# Domino_I2S.net
KiCad netlist of a schematic drawn in EAGLE
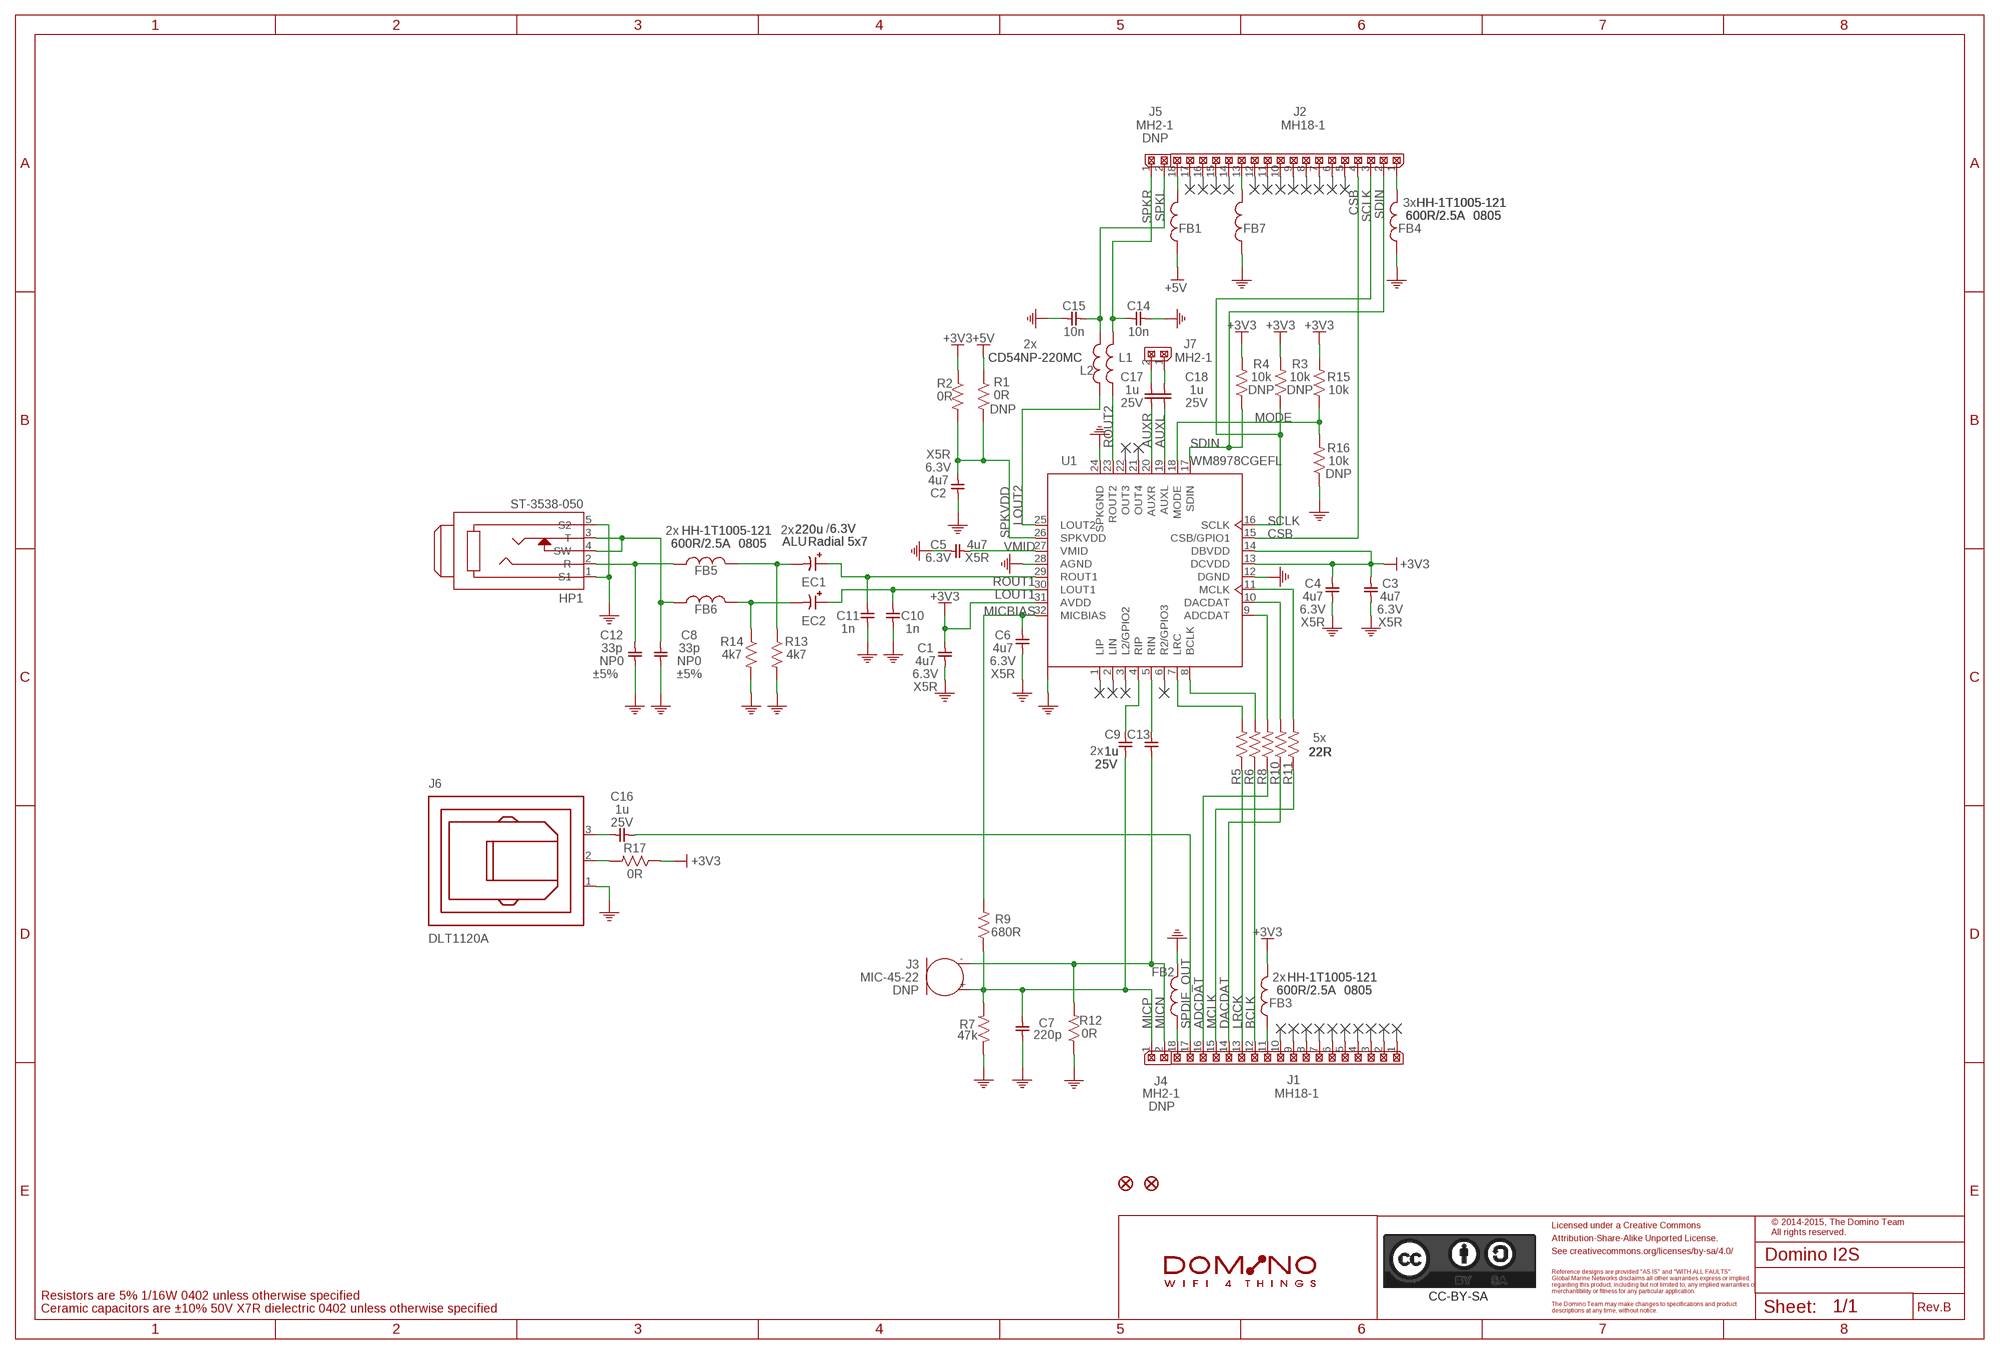
[diagram p0: schematic, sheet 1]

(export (version "E")
  (design (tool "Eeschema 10.0.6"))
  (components
    (comp (ref "C1")
      (value "4u7")
      (footprint "eagle-import:C0402")
      (fields
        (field (name "PARTNO") "C0402_4u7_X5R_10%_CER_6V3")
        (field (name "TC") "X5R")
        (field (name "VOLT") "6.3V")
      )
      (libsource (lib "eagle-import") (part "CAP_0402"))
    )
    (comp (ref "C2")
      (value "4u7")
      (footprint "eagle-import:C0402")
      (fields
        (field (name "PARTNO") "C0402_4u7_X5R_10%_CER_6V3")
        (field (name "TC") "X5R")
        (field (name "VOLT") "6.3V")
      )
      (libsource (lib "eagle-import") (part "CAP_0402"))
    )
    (comp (ref "C3")
      (value "4u7")
      (footprint "eagle-import:C0402")
      (fields
        (field (name "PARTNO") "C0402_4u7_X5R_10%_CER_6V3")
        (field (name "TC") "X5R")
        (field (name "VOLT") "6.3V")
      )
      (libsource (lib "eagle-import") (part "CAP_0402"))
    )
    (comp (ref "C4")
      (value "4u7")
      (footprint "eagle-import:C0402")
      (fields
        (field (name "PARTNO") "C0402_4u7_X5R_10%_CER_6V3")
        (field (name "TC") "X5R")
        (field (name "VOLT") "6.3V")
      )
      (libsource (lib "eagle-import") (part "CAP_0402"))
    )
    (comp (ref "C5")
      (value "4u7")
      (footprint "eagle-import:C0402")
      (fields
        (field (name "PARTNO") "C0402_4u7_X5R_10%_CER_6V3")
        (field (name "TC") "X5R")
        (field (name "VOLT") "6.3V")
      )
      (libsource (lib "eagle-import") (part "CAP_0402"))
    )
    (comp (ref "C6")
      (value "4u7")
      (footprint "eagle-import:C0402")
      (fields
        (field (name "PARTNO") "C0402_4u7_X5R_10%_CER_6V3")
        (field (name "TC") "X5R")
        (field (name "VOLT") "6.3V")
      )
      (libsource (lib "eagle-import") (part "CAP_0402"))
    )
    (comp (ref "C7")
      (value "220p")
      (footprint "eagle-import:C0402")
      (fields (field (name "PARTNO") "C0402_220p_X7R_10%_CER_50V"))
      (libsource (lib "eagle-import") (part "CAP_0402"))
    )
    (comp (ref "C8")
      (value "33p")
      (footprint "eagle-import:C0402")
      (fields
        (field (name "PARTNO") "C0402_33p_NP0_5%_CER_50V")
        (field (name "TC") "NP0")
        (field (name "TOL") "±5%")
      )
      (libsource (lib "eagle-import") (part "CAP_0402"))
    )
    (comp (ref "C9")
      (value "1u")
      (footprint "eagle-import:C0402")
      (fields (field (name "PARTNO") "C0402_1u_X7R_10%_CER_25V") (field (name "VOLT") "25V"))
      (libsource (lib "eagle-import") (part "CAP_0402"))
    )
    (comp (ref "C10")
      (value "1n")
      (footprint "eagle-import:C0402")
      (fields (field (name "PARTNO") "C0402_1n_X7R_10%_CER_50V"))
      (libsource (lib "eagle-import") (part "CAP_0402"))
    )
    (comp (ref "C11")
      (value "1n")
      (footprint "eagle-import:C0402")
      (fields (field (name "PARTNO") "C0402_1n_X7R_10%_CER_50V"))
      (libsource (lib "eagle-import") (part "CAP_0402"))
    )
    (comp (ref "C12")
      (value "33p")
      (footprint "eagle-import:C0402")
      (fields
        (field (name "PARTNO") "C0402_33p_NP0_5%_CER_50V")
        (field (name "TC") "NP0")
        (field (name "TOL") "±5%")
      )
      (libsource (lib "eagle-import") (part "CAP_0402"))
    )
    (comp (ref "C13")
      (value "1u")
      (footprint "eagle-import:C0402")
      (fields (field (name "PARTNO") "C0402_1u_X7R_10%_CER_25V") (field (name "VOLT") "25V"))
      (libsource (lib "eagle-import") (part "CAP_0402"))
    )
    (comp (ref "C14")
      (value "10n")
      (footprint "eagle-import:C0402")
      (fields (field (name "PARTNO") "C0402_10n_X7R_10%_CER_50V"))
      (libsource (lib "eagle-import") (part "CAP_0402"))
    )
    (comp (ref "C15")
      (value "10n")
      (footprint "eagle-import:C0402")
      (fields (field (name "PARTNO") "C0402_10n_X7R_10%_CER_50V"))
      (libsource (lib "eagle-import") (part "CAP_0402"))
    )
    (comp (ref "C16")
      (value "1u")
      (footprint "eagle-import:C0402")
      (fields (field (name "PARTNO") "C0402_1u_X7R_10%_CER_25V") (field (name "VOLT") "25V"))
      (libsource (lib "eagle-import") (part "CAP_0402"))
    )
    (comp (ref "C17")
      (value "1u")
      (footprint "eagle-import:C0402")
      (fields (field (name "PARTNO") "C0402_1u_X7R_10%_CER_25V") (field (name "VOLT") "25V"))
      (libsource (lib "eagle-import") (part "CAP_0402"))
    )
    (comp (ref "C18")
      (value "1u")
      (footprint "eagle-import:C0402")
      (fields (field (name "PARTNO") "C0402_1u_X7R_10%_CER_25V") (field (name "VOLT") "25V"))
      (libsource (lib "eagle-import") (part "CAP_0402"))
    )
    (comp (ref "CC-BY-SA101")
      (value "CC-BY-SA_LOGO")
      (footprint "eagle-import:CC-BY-SA_LOGO")
      (libsource (lib "eagle-import") (part "CC-BY-SA_LOGO"))
    )
    (comp (ref "EC1")
      (value "220u")
      (footprint "eagle-import:E2-5")
      (fields
        (field (name "SIZE") "Radial 5x7")
        (field (name "TYPE") "ALU")
        (field (name "PARTNO") "C2-5x7_220u_ALU_20%_RAD_6V3")
        (field (name "VOLT") "6.3V")
      )
      (libsource (lib "eagle-import") (part "CPOL_?E2-5X7"))
    )
    (comp (ref "EC2")
      (value "220u")
      (footprint "eagle-import:E2-5")
      (fields
        (field (name "SIZE") "Radial 5x7")
        (field (name "TYPE") "ALU")
        (field (name "PARTNO") "C2-5x7_220u_ALU_20%_RAD_6V3")
        (field (name "VOLT") "6.3V")
      )
      (libsource (lib "eagle-import") (part "CPOL_?E2-5X7"))
    )
    (comp (ref "F1")
      (value "FIDUCIAL")
      (footprint "eagle-import:FIDUCIAL")
      (libsource (lib "eagle-import") (part "FIDUCIAL"))
    )
    (comp (ref "F2")
      (value "FIDUCIAL")
      (footprint "eagle-import:FIDUCIAL")
      (libsource (lib "eagle-import") (part "FIDUCIAL"))
    )
    (comp (ref "FB1")
      (value "HH-1T1005-121")
      (footprint "eagle-import:FB0805")
      (fields
        (field (name "SIZE") "0805")
        (field (name "OPT") "600R/2.5A")
        (field (name "PARTNO") "HH-1T2012-601")
      )
      (libsource (lib "eagle-import") (part "FB_0805"))
    )
    (comp (ref "FB2")
      (value "HH-1T1005-121")
      (footprint "eagle-import:FB0805")
      (fields
        (field (name "SIZE") "0805")
        (field (name "OPT") "600R/2.5A")
        (field (name "PARTNO") "HH-1T2012-601")
      )
      (libsource (lib "eagle-import") (part "FB_0805"))
    )
    (comp (ref "FB3")
      (value "HH-1T1005-121")
      (footprint "eagle-import:FB0805")
      (fields
        (field (name "SIZE") "0805")
        (field (name "OPT") "600R/2.5A")
        (field (name "PARTNO") "HH-1T2012-601")
      )
      (libsource (lib "eagle-import") (part "FB_0805"))
    )
    (comp (ref "FB4")
      (value "HH-1T1005-121")
      (footprint "eagle-import:FB0805")
      (fields
        (field (name "SIZE") "0805")
        (field (name "OPT") "600R/2.5A")
        (field (name "PARTNO") "HH-1T2012-601")
      )
      (libsource (lib "eagle-import") (part "FB_0805"))
    )
    (comp (ref "FB5")
      (value "HH-1T1005-121")
      (footprint "eagle-import:FB0805")
      (fields
        (field (name "SIZE") "0805")
        (field (name "OPT") "600R/2.5A")
        (field (name "PARTNO") "HH-1T2012-601")
      )
      (libsource (lib "eagle-import") (part "FB_0805"))
    )
    (comp (ref "FB6")
      (value "HH-1T1005-121")
      (footprint "eagle-import:FB0805")
      (fields
        (field (name "SIZE") "0805")
        (field (name "OPT") "600R/2.5A")
        (field (name "PARTNO") "HH-1T2012-601")
      )
      (libsource (lib "eagle-import") (part "FB_0805"))
    )
    (comp (ref "FB7")
      (value "HH-1T1005-121")
      (footprint "eagle-import:FB0805")
      (fields
        (field (name "SIZE") "0805")
        (field (name "OPT") "600R/2.5A")
        (field (name "PARTNO") "HH-1T2012-601")
      )
      (libsource (lib "eagle-import") (part "FB_0805"))
    )
    (comp (ref "HP1")
      (value "ST-3538-050")
      (footprint "eagle-import:ST-3538-050")
      (libsource (lib "eagle-import") (part "ST-3538-050"))
    )
    (comp (ref "J1")
      (value "MH18-1")
      (footprint "eagle-import:MH18-1-0.1")
      (fields (field (name "PARTNO") "MH18-1-0.1"))
      (libsource (lib "eagle-import") (part "MH18-1"))
    )
    (comp (ref "J2")
      (value "MH18-1")
      (footprint "eagle-import:MH18-1-0.1")
      (fields (field (name "PARTNO") "MH18-1-0.1"))
      (libsource (lib "eagle-import") (part "MH18-1"))
    )
    (comp (ref "J3")
      (value "MIC-45-22")
      (footprint "eagle-import:MIC-45-22")
      (libsource (lib "eagle-import") (part "MIC-45-22"))
    )
    (comp (ref "J4")
      (value "MH2-1")
      (footprint "eagle-import:MH2-1-0.1")
      (fields (field (name "PARTNO") "MH2-1-0.1"))
      (libsource (lib "eagle-import") (part "MH2-1"))
    )
    (comp (ref "J5")
      (value "MH2-1")
      (footprint "eagle-import:MH2-1-0.1")
      (fields (field (name "PARTNO") "MH2-1-0.1"))
      (libsource (lib "eagle-import") (part "MH2-1"))
    )
    (comp (ref "J6")
      (value "DLT1120A")
      (footprint "eagle-import:DLT1120A")
      (libsource (lib "eagle-import") (part "DLT1120A"))
    )
    (comp (ref "J7")
      (value "MH2-1")
      (footprint "eagle-import:MH2-1-0.1")
      (fields (field (name "PARTNO") "MH2-1-0.1"))
      (libsource (lib "eagle-import") (part "MH2-1"))
    )
    (comp (ref "L1")
      (value "CD54NP-220MC")
      (footprint "eagle-import:CD54")
      (libsource (lib "eagle-import") (part "CD54NP-MC220"))
    )
    (comp (ref "L2")
      (value "CD54NP-220MC")
      (footprint "eagle-import:CD54")
      (libsource (lib "eagle-import") (part "CD54NP-MC220"))
    )
    (comp (ref "R1")
      (value "0R")
      (footprint "eagle-import:R0402")
      (fields (field (name "PARTNO") "R0402_0R_5%_62.5mW"))
      (libsource (lib "eagle-import") (part "RES_0402"))
    )
    (comp (ref "R2")
      (value "0R")
      (footprint "eagle-import:R0402")
      (fields (field (name "PARTNO") "R0402_0R_5%_62.5mW"))
      (libsource (lib "eagle-import") (part "RES_0402"))
    )
    (comp (ref "R3")
      (value "10k")
      (footprint "eagle-import:R0402")
      (fields (field (name "PARTNO") "R0402_10k_5%_62.5mW"))
      (libsource (lib "eagle-import") (part "RES_0402"))
    )
    (comp (ref "R4")
      (value "10k")
      (footprint "eagle-import:R0402")
      (fields (field (name "PARTNO") "R0402_10k_5%_62.5mW"))
      (libsource (lib "eagle-import") (part "RES_0402"))
    )
    (comp (ref "R5")
      (value "22R")
      (footprint "eagle-import:R0402")
      (fields (field (name "PARTNO") "R0402_22R_5%_62.5mW"))
      (libsource (lib "eagle-import") (part "RES_0402"))
    )
    (comp (ref "R6")
      (value "22R")
      (footprint "eagle-import:R0402")
      (fields (field (name "PARTNO") "R0402_22R_5%_62.5mW"))
      (libsource (lib "eagle-import") (part "RES_0402"))
    )
    (comp (ref "R7")
      (value "47k")
      (footprint "eagle-import:R0402")
      (fields (field (name "PARTNO") "R0402_47k_5%_62.5mW"))
      (libsource (lib "eagle-import") (part "RES_0402"))
    )
    (comp (ref "R8")
      (value "22R")
      (footprint "eagle-import:R0402")
      (fields (field (name "PARTNO") "R0402_22R_5%_62.5mW"))
      (libsource (lib "eagle-import") (part "RES_0402"))
    )
    (comp (ref "R9")
      (value "680R")
      (footprint "eagle-import:R0402")
      (fields (field (name "PARTNO") "R0402_680R_5%_62.5mW"))
      (libsource (lib "eagle-import") (part "RES_0402"))
    )
    (comp (ref "R10")
      (value "22R")
      (footprint "eagle-import:R0402")
      (fields (field (name "PARTNO") "R0402_22R_5%_62.5mW"))
      (libsource (lib "eagle-import") (part "RES_0402"))
    )
    (comp (ref "R11")
      (value "22R")
      (footprint "eagle-import:R0402")
      (fields (field (name "PARTNO") "R0402_22R_5%_62.5mW"))
      (libsource (lib "eagle-import") (part "RES_0402"))
    )
    (comp (ref "R12")
      (value "0R")
      (footprint "eagle-import:R0402")
      (fields (field (name "PARTNO") "R0402_0R_5%_62.5mW"))
      (libsource (lib "eagle-import") (part "RES_0402"))
    )
    (comp (ref "R13")
      (value "4k7")
      (footprint "eagle-import:R0402")
      (fields (field (name "PARTNO") "R0402_4k7_5%_62.5mW"))
      (libsource (lib "eagle-import") (part "RES_0402"))
    )
    (comp (ref "R14")
      (value "4k7")
      (footprint "eagle-import:R0402")
      (fields (field (name "PARTNO") "R0402_4k7_5%_62.5mW"))
      (libsource (lib "eagle-import") (part "RES_0402"))
    )
    (comp (ref "R15")
      (value "10k")
      (footprint "eagle-import:R0402")
      (fields (field (name "PARTNO") "R0402_10k_5%_62.5mW"))
      (libsource (lib "eagle-import") (part "RES_0402"))
    )
    (comp (ref "R16")
      (value "10k")
      (footprint "eagle-import:R0402")
      (fields (field (name "PARTNO") "R0402_10k_5%_62.5mW"))
      (libsource (lib "eagle-import") (part "RES_0402"))
    )
    (comp (ref "R17")
      (value "0R")
      (footprint "eagle-import:R0402")
      (fields (field (name "PARTNO") "R0402_0R_5%_62.5mW"))
      (libsource (lib "eagle-import") (part "RES_0402"))
    )
    (comp (ref "S101")
      (value "DOMINO_LOGO")
      (footprint "eagle-import:DOMINO_LOGO")
      (libsource (lib "eagle-import") (part "DOMINO_LOGO"))
    )
    (comp (ref "U1")
      (value "WM8978CGEFL")
      (footprint "eagle-import:QFN-32_EP_5X5")
      (libsource (lib "eagle-import") (part "WM8978CGEFL"))
    )
  )
  (nets
    (net (code "1") (name "+3V3") (class "Default")
      (node (ref "C1") (pin "1") (pinfunction "1_1") (pintype "passive"))
      (node (ref "C3") (pin "1") (pinfunction "1_1") (pintype "passive"))
      (node (ref "C4") (pin "1") (pinfunction "1_1") (pintype "passive"))
      (node (ref "FB3") (pin "2") (pinfunction "2_2") (pintype "passive"))
      (node (ref "R15") (pin "2") (pinfunction "2_2") (pintype "passive"))
      (node (ref "R17") (pin "1") (pinfunction "1_1") (pintype "passive"))
      (node (ref "R2") (pin "1") (pinfunction "1_1") (pintype "passive"))
      (node (ref "R3") (pin "2") (pinfunction "2_2") (pintype "passive"))
      (node (ref "R4") (pin "2") (pinfunction "2_2") (pintype "passive"))
      (node (ref "U1") (pin "13") (pinfunction "DCVDD_13") (pintype "power_in"))
      (node (ref "U1") (pin "14") (pinfunction "DBVDD_14") (pintype "power_in"))
      (node (ref "U1") (pin "31") (pinfunction "AVDD_31") (pintype "power_in"))
    )
    (net (code "2") (name "+5V") (class "Default")
      (node (ref "FB1") (pin "1") (pinfunction "1_1") (pintype "passive"))
      (node (ref "R1") (pin "1") (pinfunction "1_1") (pintype "passive"))
    )
    (net (code "3") (name "/ADCDAT") (class "Default")
      (node (ref "J1") (pin "16") (pinfunction "16_16") (pintype "passive"))
      (node (ref "R8") (pin "1") (pinfunction "1_1") (pintype "passive"))
    )
    (net (code "4") (name "/AUXL") (class "Default")
      (node (ref "C18") (pin "2") (pinfunction "2_2") (pintype "passive"))
      (node (ref "U1") (pin "19") (pinfunction "AUXL_19") (pintype "passive"))
    )
    (net (code "5") (name "/AUXR") (class "Default")
      (node (ref "C17") (pin "2") (pinfunction "2_2") (pintype "passive"))
      (node (ref "U1") (pin "20") (pinfunction "AUXR_20") (pintype "passive"))
    )
    (net (code "6") (name "/BCLK") (class "Default")
      (node (ref "J1") (pin "12") (pinfunction "12_12") (pintype "passive"))
      (node (ref "R6") (pin "1") (pinfunction "1_1") (pintype "passive"))
    )
    (net (code "7") (name "/CSB") (class "Default")
      (node (ref "J2") (pin "4") (pinfunction "4_4") (pintype "passive"))
      (node (ref "U1") (pin "15") (pinfunction "CSB/GPIO1_15") (pintype "bidirectional"))
    )
    (net (code "8") (name "/DACDAT") (class "Default")
      (node (ref "J1") (pin "14") (pinfunction "14_14") (pintype "passive"))
      (node (ref "R10") (pin "1") (pinfunction "1_1") (pintype "passive"))
    )
    (net (code "9") (name "/LOUT1") (class "Default")
      (node (ref "C10") (pin "1") (pinfunction "1_1") (pintype "passive"))
      (node (ref "EC2") (pin "1") (pinfunction "+_1") (pintype "passive"))
      (node (ref "U1") (pin "30") (pinfunction "LOUT1_30") (pintype "passive"))
    )
    (net (code "10") (name "/LOUT2") (class "Default")
      (node (ref "L2") (pin "1") (pinfunction "1_1") (pintype "passive"))
      (node (ref "U1") (pin "25") (pinfunction "LOUT2_25") (pintype "passive"))
    )
    (net (code "11") (name "/LRCK") (class "Default")
      (node (ref "J1") (pin "13") (pinfunction "13_13") (pintype "passive"))
      (node (ref "R5") (pin "1") (pinfunction "1_1") (pintype "passive"))
    )
    (net (code "12") (name "/MCLK") (class "Default")
      (node (ref "J1") (pin "15") (pinfunction "15_15") (pintype "passive"))
      (node (ref "R11") (pin "1") (pinfunction "1_1") (pintype "passive"))
    )
    (net (code "13") (name "/MICBIAS") (class "Default")
      (node (ref "C6") (pin "1") (pinfunction "1_1") (pintype "passive"))
      (node (ref "R9") (pin "2") (pinfunction "2_2") (pintype "passive"))
      (node (ref "U1") (pin "32") (pinfunction "MICBIAS_32") (pintype "passive"))
    )
    (net (code "14") (name "/MICN") (class "Default")
      (node (ref "C13") (pin "2") (pinfunction "2_2") (pintype "passive"))
      (node (ref "J3") (pin "-") (pinfunction "-_-") (pintype "passive"))
      (node (ref "J4") (pin "2") (pinfunction "2_2") (pintype "passive"))
      (node (ref "R12") (pin "2") (pinfunction "2_2") (pintype "passive"))
    )
    (net (code "15") (name "/MICP") (class "Default")
      (node (ref "C7") (pin "1") (pinfunction "1_1") (pintype "passive"))
      (node (ref "C9") (pin "2") (pinfunction "2_2") (pintype "passive"))
      (node (ref "J3") (pin "+") (pinfunction "+_+") (pintype "passive"))
      (node (ref "J4") (pin "1") (pinfunction "1_1") (pintype "passive"))
      (node (ref "R7") (pin "2") (pinfunction "2_2") (pintype "passive"))
      (node (ref "R9") (pin "1") (pinfunction "1_1") (pintype "passive"))
    )
    (net (code "16") (name "/MODE") (class "Default")
      (node (ref "R15") (pin "1") (pinfunction "1_1") (pintype "passive"))
      (node (ref "R16") (pin "2") (pinfunction "2_2") (pintype "passive"))
      (node (ref "U1") (pin "18") (pinfunction "MODE_18") (pintype "input"))
    )
    (net (code "17") (name "/ROUT1") (class "Default")
      (node (ref "C11") (pin "1") (pinfunction "1_1") (pintype "passive"))
      (node (ref "EC1") (pin "1") (pinfunction "+_1") (pintype "passive"))
      (node (ref "U1") (pin "29") (pinfunction "ROUT1_29") (pintype "passive"))
    )
    (net (code "18") (name "/ROUT2") (class "Default")
      (node (ref "L1") (pin "1") (pinfunction "1_1") (pintype "passive"))
      (node (ref "U1") (pin "23") (pinfunction "ROUT2_23") (pintype "passive"))
    )
    (net (code "19") (name "/SCLK") (class "Default")
      (node (ref "J2") (pin "3") (pinfunction "3_3") (pintype "passive"))
      (node (ref "R3") (pin "1") (pinfunction "1_1") (pintype "passive"))
      (node (ref "U1") (pin "16") (pinfunction "SCLK_16") (pintype "input"))
    )
    (net (code "20") (name "/SDIN") (class "Default")
      (node (ref "J2") (pin "2") (pinfunction "2_2") (pintype "passive"))
      (node (ref "R4") (pin "1") (pinfunction "1_1") (pintype "passive"))
      (node (ref "U1") (pin "17") (pinfunction "SDIN_17") (pintype "bidirectional"))
    )
    (net (code "21") (name "/SPDIF_OUT") (class "Default")
      (node (ref "C16") (pin "2") (pinfunction "2_2") (pintype "passive"))
      (node (ref "J1") (pin "17") (pinfunction "17_17") (pintype "passive"))
    )
    (net (code "22") (name "/SPKL") (class "Default")
      (node (ref "C15") (pin "1") (pinfunction "1_1") (pintype "passive"))
      (node (ref "J5") (pin "2") (pinfunction "2_2") (pintype "passive"))
      (node (ref "L2") (pin "2") (pinfunction "2_2") (pintype "passive"))
    )
    (net (code "23") (name "/SPKR") (class "Default")
      (node (ref "C14") (pin "1") (pinfunction "1_1") (pintype "passive"))
      (node (ref "J5") (pin "1") (pinfunction "1_1") (pintype "passive"))
      (node (ref "L1") (pin "2") (pinfunction "2_2") (pintype "passive"))
    )
    (net (code "24") (name "/SPKVDD") (class "Default")
      (node (ref "C2") (pin "2") (pinfunction "2_2") (pintype "passive"))
      (node (ref "R1") (pin "2") (pinfunction "2_2") (pintype "passive"))
      (node (ref "R2") (pin "2") (pinfunction "2_2") (pintype "passive"))
      (node (ref "U1") (pin "26") (pinfunction "SPKVDD_26") (pintype "power_in"))
    )
    (net (code "25") (name "/VMID") (class "Default")
      (node (ref "C5") (pin "2") (pinfunction "2_2") (pintype "passive"))
      (node (ref "U1") (pin "27") (pinfunction "VMID_27") (pintype "passive"))
    )
    (net (code "26") (name "GND") (class "Default")
      (node (ref "C1") (pin "2") (pinfunction "2_2") (pintype "passive"))
      (node (ref "C10") (pin "2") (pinfunction "2_2") (pintype "passive"))
      (node (ref "C11") (pin "2") (pinfunction "2_2") (pintype "passive"))
      (node (ref "C12") (pin "1") (pinfunction "1_1") (pintype "passive"))
      (node (ref "C14") (pin "2") (pinfunction "2_2") (pintype "passive"))
      (node (ref "C15") (pin "2") (pinfunction "2_2") (pintype "passive"))
      (node (ref "C2") (pin "1") (pinfunction "1_1") (pintype "passive"))
      (node (ref "C3") (pin "2") (pinfunction "2_2") (pintype "passive"))
      (node (ref "C4") (pin "2") (pinfunction "2_2") (pintype "passive"))
      (node (ref "C5") (pin "1") (pinfunction "1_1") (pintype "passive"))
      (node (ref "C6") (pin "2") (pinfunction "2_2") (pintype "passive"))
      (node (ref "C7") (pin "2") (pinfunction "2_2") (pintype "passive"))
      (node (ref "C8") (pin "1") (pinfunction "1_1") (pintype "passive"))
      (node (ref "FB2") (pin "2") (pinfunction "2_2") (pintype "passive"))
      (node (ref "FB4") (pin "1") (pinfunction "1_1") (pintype "passive"))
      (node (ref "FB7") (pin "1") (pinfunction "1_1") (pintype "passive"))
      (node (ref "HP1") (pin "1") (pinfunction "S1_1") (pintype "passive"))
      (node (ref "HP1") (pin "5") (pinfunction "S2_5") (pintype "passive"))
      (node (ref "J6") (pin "1") (pinfunction "GND_1") (pintype "power_in"))
      (node (ref "R12") (pin "1") (pinfunction "1_1") (pintype "passive"))
      (node (ref "R13") (pin "2") (pinfunction "2_2") (pintype "passive"))
      (node (ref "R14") (pin "2") (pinfunction "2_2") (pintype "passive"))
      (node (ref "R16") (pin "1") (pinfunction "1_1") (pintype "passive"))
      (node (ref "R7") (pin "1") (pinfunction "1_1") (pintype "passive"))
      (node (ref "U1") (pin "12") (pinfunction "DGND_12") (pintype "power_in"))
      (node (ref "U1") (pin "24") (pinfunction "SPKGND_24") (pintype "power_in"))
      (node (ref "U1") (pin "28") (pinfunction "AGND_28") (pintype "power_in"))
      (node (ref "U1") (pin "PAD") (pinfunction "PAD_PAD") (pintype "power_in"))
    )
    (net (code "27") (name "Net-(C17-Pad1)") (class "Default")
      (node (ref "C17") (pin "1") (pinfunction "1_1") (pintype "passive"))
      (node (ref "J7") (pin "2") (pinfunction "2_2") (pintype "passive"))
    )
    (net (code "28") (name "Net-(C18-Pad1)") (class "Default")
      (node (ref "C18") (pin "1") (pinfunction "1_1") (pintype "passive"))
      (node (ref "J7") (pin "1") (pinfunction "1_1") (pintype "passive"))
    )
    (net (code "29") (name "Net-(EC1--)") (class "Default")
      (node (ref "EC1") (pin "2") (pinfunction "-_2") (pintype "passive"))
      (node (ref "FB5") (pin "2") (pinfunction "2_2") (pintype "passive"))
      (node (ref "R13") (pin "1") (pinfunction "1_1") (pintype "passive"))
    )
    (net (code "30") (name "Net-(EC2--)") (class "Default")
      (node (ref "EC2") (pin "2") (pinfunction "-_2") (pintype "passive"))
      (node (ref "FB6") (pin "2") (pinfunction "2_2") (pintype "passive"))
      (node (ref "R14") (pin "1") (pinfunction "1_1") (pintype "passive"))
    )
    (net (code "31") (name "Net-(FB1-Pad2)") (class "Default")
      (node (ref "FB1") (pin "2") (pinfunction "2_2") (pintype "passive"))
      (node (ref "J2") (pin "18") (pinfunction "18_18") (pintype "passive"))
    )
    (net (code "32") (name "Net-(FB2-Pad1)") (class "Default")
      (node (ref "FB2") (pin "1") (pinfunction "1_1") (pintype "passive"))
      (node (ref "J1") (pin "18") (pinfunction "18_18") (pintype "passive"))
    )
    (net (code "33") (name "Net-(FB3-Pad1)") (class "Default")
      (node (ref "FB3") (pin "1") (pinfunction "1_1") (pintype "passive"))
      (node (ref "J1") (pin "11") (pinfunction "11_11") (pintype "passive"))
    )
    (net (code "34") (name "Net-(FB4-Pad2)") (class "Default")
      (node (ref "FB4") (pin "2") (pinfunction "2_2") (pintype "passive"))
      (node (ref "J2") (pin "1") (pinfunction "1_1") (pintype "passive"))
    )
    (net (code "35") (name "Net-(FB7-Pad2)") (class "Default")
      (node (ref "FB7") (pin "2") (pinfunction "2_2") (pintype "passive"))
      (node (ref "J2") (pin "13") (pinfunction "13_13") (pintype "passive"))
    )
    (net (code "36") (name "Net-(HP1-R)") (class "Default")
      (node (ref "C12") (pin "2") (pinfunction "2_2") (pintype "passive"))
      (node (ref "FB5") (pin "1") (pinfunction "1_1") (pintype "passive"))
      (node (ref "HP1") (pin "2") (pinfunction "R_2") (pintype "passive"))
    )
    (net (code "37") (name "Net-(HP1-SW)") (class "Default")
      (node (ref "C8") (pin "2") (pinfunction "2_2") (pintype "passive"))
      (node (ref "FB6") (pin "1") (pinfunction "1_1") (pintype "passive"))
      (node (ref "HP1") (pin "3") (pinfunction "T_3") (pintype "passive"))
      (node (ref "HP1") (pin "4") (pinfunction "SW_4") (pintype "passive"))
    )
    (net (code "38") (name "Net-(J6-VCC)") (class "Default")
      (node (ref "J6") (pin "2") (pinfunction "VCC_2") (pintype "power_in"))
      (node (ref "R17") (pin "2") (pinfunction "2_2") (pintype "passive"))
    )
    (net (code "39") (name "Net-(J6-VIN)") (class "Default")
      (node (ref "C16") (pin "1") (pinfunction "1_1") (pintype "passive"))
      (node (ref "J6") (pin "3") (pinfunction "VIN_3") (pintype "passive"))
    )
    (net (code "40") (name "Net-(U1-ADCDAT)") (class "Default")
      (node (ref "R8") (pin "2") (pinfunction "2_2") (pintype "passive"))
      (node (ref "U1") (pin "9") (pinfunction "ADCDAT_9") (pintype "output"))
    )
    (net (code "41") (name "Net-(U1-BCLK)") (class "Default")
      (node (ref "R6") (pin "2") (pinfunction "2_2") (pintype "passive"))
      (node (ref "U1") (pin "8") (pinfunction "BCLK_8") (pintype "bidirectional"))
    )
    (net (code "42") (name "Net-(U1-DACDAT)") (class "Default")
      (node (ref "R10") (pin "2") (pinfunction "2_2") (pintype "passive"))
      (node (ref "U1") (pin "10") (pinfunction "DACDAT_10") (pintype "input"))
    )
    (net (code "43") (name "Net-(U1-LRC)") (class "Default")
      (node (ref "R5") (pin "2") (pinfunction "2_2") (pintype "passive"))
      (node (ref "U1") (pin "7") (pinfunction "LRC_7") (pintype "bidirectional"))
    )
    (net (code "44") (name "Net-(U1-MCLK)") (class "Default")
      (node (ref "R11") (pin "2") (pinfunction "2_2") (pintype "passive"))
      (node (ref "U1") (pin "11") (pinfunction "MCLK_11") (pintype "input"))
    )
    (net (code "45") (name "Net-(U1-RIN)") (class "Default")
      (node (ref "C13") (pin "1") (pinfunction "1_1") (pintype "passive"))
      (node (ref "U1") (pin "5") (pinfunction "RIN_5") (pintype "passive"))
    )
    (net (code "46") (name "Net-(U1-RIP)") (class "Default")
      (node (ref "C9") (pin "1") (pinfunction "1_1") (pintype "passive"))
      (node (ref "U1") (pin "4") (pinfunction "RIP_4") (pintype "passive"))
    )
    (net (code "47") (name "unconnected-(J1-Pad1)") (class "Default")
      (node (ref "J1") (pin "1") (pinfunction "1_1") (pintype "passive"))
    )
    (net (code "48") (name "unconnected-(J1-Pad2)") (class "Default")
      (node (ref "J1") (pin "2") (pinfunction "2_2") (pintype "passive"))
    )
    (net (code "49") (name "unconnected-(J1-Pad3)") (class "Default")
      (node (ref "J1") (pin "3") (pinfunction "3_3") (pintype "passive"))
    )
    (net (code "50") (name "unconnected-(J1-Pad4)") (class "Default")
      (node (ref "J1") (pin "4") (pinfunction "4_4") (pintype "passive"))
    )
    (net (code "51") (name "unconnected-(J1-Pad5)") (class "Default")
      (node (ref "J1") (pin "5") (pinfunction "5_5") (pintype "passive"))
    )
    (net (code "52") (name "unconnected-(J1-Pad6)") (class "Default")
      (node (ref "J1") (pin "6") (pinfunction "6_6") (pintype "passive"))
    )
    (net (code "53") (name "unconnected-(J1-Pad7)") (class "Default")
      (node (ref "J1") (pin "7") (pinfunction "7_7") (pintype "passive"))
    )
    (net (code "54") (name "unconnected-(J1-Pad8)") (class "Default")
      (node (ref "J1") (pin "8") (pinfunction "8_8") (pintype "passive"))
    )
    (net (code "55") (name "unconnected-(J1-Pad9)") (class "Default")
      (node (ref "J1") (pin "9") (pinfunction "9_9") (pintype "passive"))
    )
    (net (code "56") (name "unconnected-(J1-Pad10)") (class "Default")
      (node (ref "J1") (pin "10") (pinfunction "10_10") (pintype "passive"))
    )
    (net (code "57") (name "unconnected-(J2-Pad5)") (class "Default")
      (node (ref "J2") (pin "5") (pinfunction "5_5") (pintype "passive"))
    )
    (net (code "58") (name "unconnected-(J2-Pad6)") (class "Default")
      (node (ref "J2") (pin "6") (pinfunction "6_6") (pintype "passive"))
    )
    (net (code "59") (name "unconnected-(J2-Pad7)") (class "Default")
      (node (ref "J2") (pin "7") (pinfunction "7_7") (pintype "passive"))
    )
    (net (code "60") (name "unconnected-(J2-Pad8)") (class "Default")
      (node (ref "J2") (pin "8") (pinfunction "8_8") (pintype "passive"))
    )
    (net (code "61") (name "unconnected-(J2-Pad9)") (class "Default")
      (node (ref "J2") (pin "9") (pinfunction "9_9") (pintype "passive"))
    )
    (net (code "62") (name "unconnected-(J2-Pad10)") (class "Default")
      (node (ref "J2") (pin "10") (pinfunction "10_10") (pintype "passive"))
    )
    (net (code "63") (name "unconnected-(J2-Pad11)") (class "Default")
      (node (ref "J2") (pin "11") (pinfunction "11_11") (pintype "passive"))
    )
    (net (code "64") (name "unconnected-(J2-Pad12)") (class "Default")
      (node (ref "J2") (pin "12") (pinfunction "12_12") (pintype "passive"))
    )
    (net (code "65") (name "unconnected-(J2-Pad14)") (class "Default")
      (node (ref "J2") (pin "14") (pinfunction "14_14") (pintype "passive"))
    )
    (net (code "66") (name "unconnected-(J2-Pad15)") (class "Default")
      (node (ref "J2") (pin "15") (pinfunction "15_15") (pintype "passive"))
    )
    (net (code "67") (name "unconnected-(J2-Pad16)") (class "Default")
      (node (ref "J2") (pin "16") (pinfunction "16_16") (pintype "passive"))
    )
    (net (code "68") (name "unconnected-(J2-Pad17)") (class "Default")
      (node (ref "J2") (pin "17") (pinfunction "17_17") (pintype "passive"))
    )
    (net (code "69") (name "unconnected-(U1-L2{slash}GPIO2-Pad3)") (class "Default")
      (node (ref "U1") (pin "3") (pinfunction "L2/GPIO2_3") (pintype "passive"))
    )
    (net (code "70") (name "unconnected-(U1-LIN-Pad2)") (class "Default")
      (node (ref "U1") (pin "2") (pinfunction "LIN_2") (pintype "passive"))
    )
    (net (code "71") (name "unconnected-(U1-LIP-Pad1)") (class "Default")
      (node (ref "U1") (pin "1") (pinfunction "LIP_1") (pintype "passive"))
    )
    (net (code "72") (name "unconnected-(U1-OUT3-Pad22)") (class "Default")
      (node (ref "U1") (pin "22") (pinfunction "OUT3_22") (pintype "passive"))
    )
    (net (code "73") (name "unconnected-(U1-OUT4-Pad21)") (class "Default")
      (node (ref "U1") (pin "21") (pinfunction "OUT4_21") (pintype "passive"))
    )
    (net (code "74") (name "unconnected-(U1-R2{slash}GPIO3-Pad6)") (class "Default")
      (node (ref "U1") (pin "6") (pinfunction "R2/GPIO3_6") (pintype "passive"))
    )
  )
)
